# BlinkyBoard_New.net
KiCad netlist of a schematic drawn in EAGLE
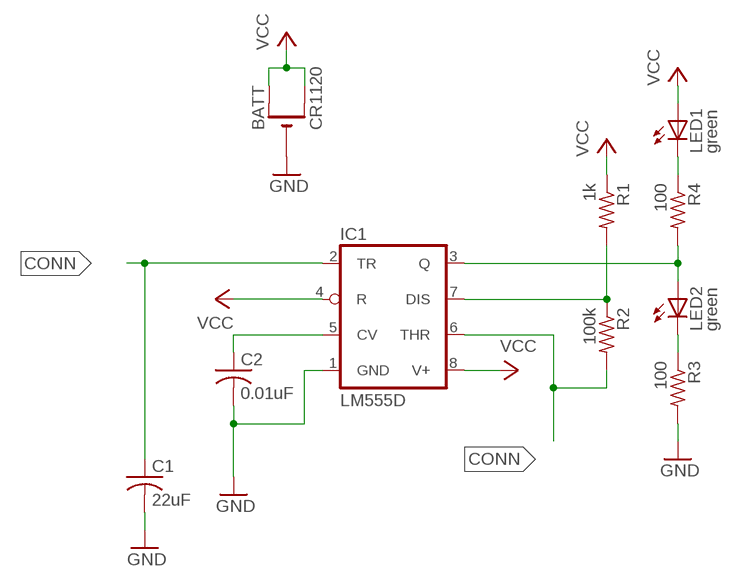
[diagram p0: schematic, sheet 1]

(export (version "E")
  (design (tool "Eeschema 10.0.6"))
  (components
    (comp (ref "BATT")
      (value "CR1120")
      (footprint "eagle-import:CR1220-SMD")
      (libsource (lib "eagle-import") (part "CR1220SMT"))
    )
    (comp (ref "C1")
      (value "22uF")
      (footprint "eagle-import:C0805")
      (fields (field (name "MF") "AVX CORPORATION") (field (name "MPN") "08056D226MAT2A"))
      (libsource (lib "eagle-import") (part "C-USC0805"))
    )
    (comp (ref "C2")
      (value "0.01uF")
      (footprint "eagle-import:C0805")
      (fields (field (name "MPN") "C0805X103K1RAC3316"))
      (libsource (lib "eagle-import") (part "C-USC0805"))
    )
    (comp (ref "IC1")
      (value "LM555D")
      (footprint "eagle-import:SO08")
      (fields (field (name "MPN") "NE555DR"))
      (libsource (lib "eagle-import") (part "555DLM"))
    )
    (comp (ref "LED1")
      (value "green")
      (footprint "eagle-import:CHIPLED_0805")
      (fields (field (name "MPN") "MCL-S270GC"))
      (libsource (lib "eagle-import") (part "LEDCHIPLED_0805"))
    )
    (comp (ref "LED2")
      (value "green")
      (footprint "eagle-import:CHIPLED_0805")
      (fields (field (name "MPN") "MCL-S270GC"))
      (libsource (lib "eagle-import") (part "LEDCHIPLED_0805"))
    )
    (comp (ref "R1")
      (value "1k")
      (footprint "eagle-import:R0805")
      (fields (field (name "MPN") "CRCW08051K00FKTC"))
      (libsource (lib "eagle-import") (part "R-US_R0805"))
    )
    (comp (ref "R2")
      (value "100k")
      (footprint "eagle-import:R0805")
      (fields (field (name "MF") "VISHAY/DALE") (field (name "MPN") "CRCW0805100KFKTA"))
      (libsource (lib "eagle-import") (part "R-US_R0805"))
    )
    (comp (ref "R3")
      (value "100")
      (footprint "eagle-import:R0805")
      (fields (field (name "MF") "VISHAY/DALE") (field (name "MPN") "CRCW0805100RFKTA"))
      (libsource (lib "eagle-import") (part "R-US_R0805"))
    )
    (comp (ref "R4")
      (value "100")
      (footprint "eagle-import:R0805")
      (fields (field (name "MF") "VISHAY/DALE") (field (name "MPN") "CRCW0805100RFKTA"))
      (libsource (lib "eagle-import") (part "R-US_R0805"))
    )
  )
  (nets
    (net (code "1") (name "CONN") (class "Default")
      (node (ref "C1") (pin "1") (pinfunction "1_1") (pintype "passive"))
      (node (ref "IC1") (pin "2") (pinfunction "TR_2") (pintype "input"))
      (node (ref "IC1") (pin "6") (pinfunction "THR_6") (pintype "input"))
      (node (ref "R2") (pin "2") (pinfunction "2_2") (pintype "passive"))
    )
    (net (code "2") (name "GND") (class "Default")
      (node (ref "BATT") (pin "-") (pinfunction "-_-") (pintype "passive"))
      (node (ref "C1") (pin "2") (pinfunction "2_2") (pintype "passive"))
      (node (ref "C2") (pin "2") (pinfunction "2_2") (pintype "passive"))
      (node (ref "IC1") (pin "1") (pinfunction "GND_1") (pintype "power_in"))
      (node (ref "R3") (pin "2") (pinfunction "2_2") (pintype "passive"))
    )
    (net (code "3") (name "Net-(IC1-CV)") (class "Default")
      (node (ref "C2") (pin "1") (pinfunction "1_1") (pintype "passive"))
      (node (ref "IC1") (pin "5") (pinfunction "CV_5") (pintype "input"))
    )
    (net (code "4") (name "Net-(IC1-DIS)") (class "Default")
      (node (ref "IC1") (pin "7") (pinfunction "DIS_7") (pintype "input"))
      (node (ref "R1") (pin "2") (pinfunction "2_2") (pintype "passive"))
      (node (ref "R2") (pin "1") (pinfunction "1_1") (pintype "passive"))
    )
    (net (code "5") (name "Net-(IC1-Q)") (class "Default")
      (node (ref "IC1") (pin "3") (pinfunction "Q_3") (pintype "output"))
      (node (ref "LED2") (pin "A") (pinfunction "A_A") (pintype "passive"))
      (node (ref "R4") (pin "2") (pinfunction "2_2") (pintype "passive"))
    )
    (net (code "6") (name "Net-(LED1-PadC)") (class "Default")
      (node (ref "LED1") (pin "C") (pinfunction "C_C") (pintype "passive"))
      (node (ref "R4") (pin "1") (pinfunction "1_1") (pintype "passive"))
    )
    (net (code "7") (name "Net-(LED2-PadC)") (class "Default")
      (node (ref "LED2") (pin "C") (pinfunction "C_C") (pintype "passive"))
      (node (ref "R3") (pin "1") (pinfunction "1_1") (pintype "passive"))
    )
    (net (code "8") (name "VCC") (class "Default")
      (node (ref "BATT") (pin "+$1") (pinfunction "+_+$1") (pintype "passive"))
      (node (ref "BATT") (pin "+$2") (pinfunction "+1_+$2") (pintype "passive"))
      (node (ref "IC1") (pin "4") (pinfunction "R_4") (pintype "input"))
      (node (ref "IC1") (pin "8") (pinfunction "V+_8") (pintype "power_in"))
      (node (ref "LED1") (pin "A") (pinfunction "A_A") (pintype "passive"))
      (node (ref "R1") (pin "1") (pinfunction "1_1") (pintype "passive"))
    )
  )
)
